# RTD.net
KiCad netlist of a schematic drawn in Altium Designer
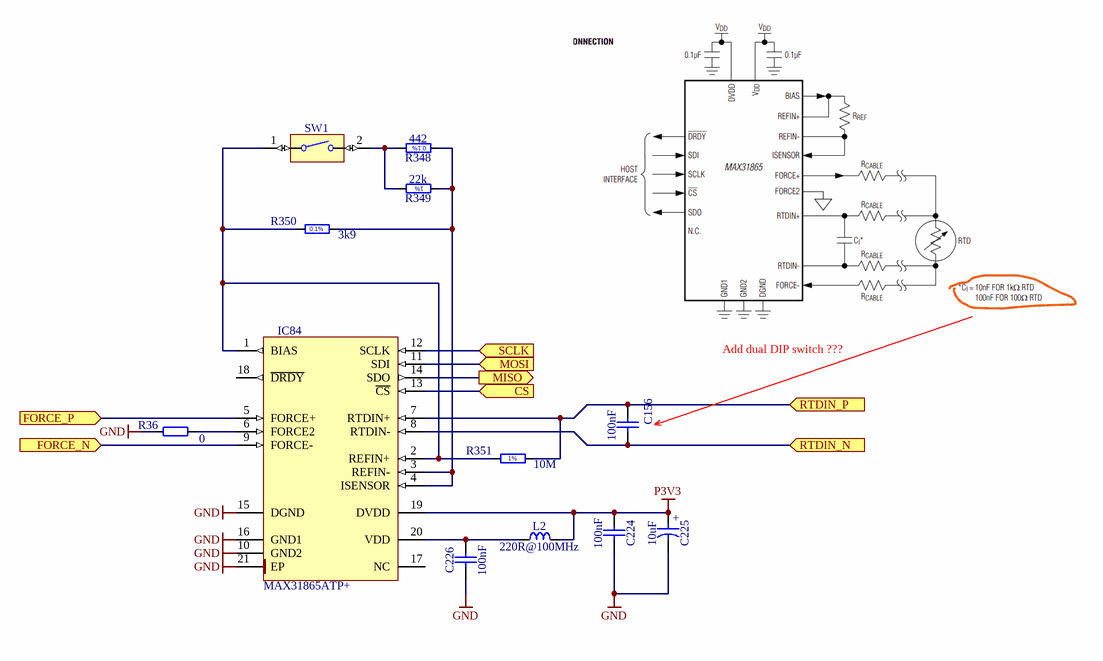
[diagram p0: RTD.SchDoc]

(export (version "E")
  (design (tool "Eeschema 10.0.6"))
  (components
    (comp (ref "C156")
      (value "100nF")
      (footprint "CAPC1005X55N")
      (description "Non-polarised capacitor")
      (fields
        (field (name "PART NUMBER") "CC0402_100NF_16V_10%_X5R")
        (field (name "VOLTAGE") "16V")
        (field (name "AUTHOR") "CERN DEM JLC")
      )
      (libsource (lib "Capacitors") (part "Capacitor - non polarized"))
    )
    (comp (ref "C224")
      (value "100nF")
      (footprint "CAPC1005X55N")
      (description "Non-polarised capacitor")
      (fields
        (field (name "PART NUMBER") "CC0402_100NF_16V_10%_X5R")
        (field (name "VOLTAGE") "16V")
        (field (name "AUTHOR") "CERN DEM JLC")
      )
      (libsource (lib "Capacitors") (part "Capacitor - non polarized"))
    )
    (comp (ref "C225")
      (value "10uF")
      (footprint "CAPMP3216X180N")
      (description "Polarised capacitor")
      (fields
        (field (name "PART NUMBER") "CTE3216-18_10UF_16V_20%_AVX_TCJ")
        (field (name "VOLTAGE") "16V")
        (field (name "AUTHOR") "CERN DEM JLC")
      )
      (libsource (lib "Capacitors") (part "Capacitor - polarized"))
    )
    (comp (ref "C226")
      (value "100nF")
      (footprint "CAPC1005X55N")
      (description "Non-polarised capacitor")
      (fields
        (field (name "PART NUMBER") "CC0402_100NF_16V_10%_X5R")
        (field (name "VOLTAGE") "16V")
        (field (name "AUTHOR") "CERN DEM JLC")
      )
      (libsource (lib "Capacitors") (part "Capacitor - non polarized"))
    )
    (comp (ref "IC84")
      (value "MAX31865ATP+")
      (footprint "QFN65P500X500X80-21N-S335")
      (description "RTD-to-Digital Converter")
      (fields (field (name "MANUFACTURER") "MAXIM") (field (name "AUTHOR") "CERN DEM MR"))
      (libsource (lib "ICs And Semiconductors") (part "MAX31865ATP+"))
    )
    (comp (ref "L2")
      (value "220R@100MHz")
      (footprint "INDC1005X55N")
      (description "Inductor")
      (fields
        (field (name "PART NUMBER") "IND0402_MURATA_BLM15HB221SN1")
        (field (name "POWER") "250mA")
        (field (name "AUTHOR") "CERN DEM JLC")
      )
      (libsource (lib "Inductors & Transformers") (part "Inductor"))
    )
    (comp (ref "R36")
      (value "0")
      (footprint "RESC1005X40N")
      (description "Resistor")
      (fields
        (field (name "PART NUMBER") "R0402_0R_JUMPER")
        (field (name "MANUFACTURER") "GENERIC")
        (field (name "AUTHOR") "CERN DEM JLC")
      )
      (libsource (lib "Resistors") (part "Resistor"))
    )
    (comp (ref "R348")
      (value "442")
      (footprint "RESC1608X55N")
      (description "Resistor - 0.1%")
      (fields
        (field (name "PART NUMBER") "R0603_442R_0.1%_0.063W_25PPM")
        (field (name "POWER") "0.063W")
        (field (name "AUTHOR") "GK")
      )
      (libsource (lib "LIBRARY_SCH") (part "RES_0603_442R_0.1%_25ppm"))
    )
    (comp (ref "R349")
      (value "22k")
      (footprint "RESC1005X40N")
      (description "Resistor - 1%")
      (fields
        (field (name "PART NUMBER") "R0402_22K_1%_0.0625W_100PPM")
        (field (name "POWER") "0.0625W")
        (field (name "AUTHOR") "CERN DEM JLC")
      )
      (libsource (lib "Resistors") (part "Resistor - 1%"))
    )
    (comp (ref "R350")
      (value "3k9")
      (footprint "RESC1608X55N")
      (description "Resistor - 0.1%")
      (fields
        (field (name "PART NUMBER") "R0603_3k9_0.1%_0.063W_10PPM")
        (field (name "POWER") "0.063W")
        (field (name "AUTHOR") "GK")
      )
      (libsource (lib "LIBRARY_SCH") (part "RES_0603_3k9_0.1%_10ppm"))
    )
    (comp (ref "R351")
      (value "10M")
      (footprint "RESC1608X55N")
      (description "Resistor - 1%")
      (fields
        (field (name "PART NUMBER") "R0603_10M_1%_0.1W_100PPM")
        (field (name "POWER") "0.1W")
        (field (name "AUTHOR") "CERN DEM JLC")
      )
      (libsource (lib "Resistors") (part "Resistor - 1%"))
    )
    (comp (ref "SW1")
      (value "Switch")
      (footprint "SW_OMRON_A6SN-1101")
      (description "1 Ways SPST DIP Switch")
      (fields
        (field (name "PART NUMBER") "SW_OMRON_A6SN-1101")
        (field (name "MANUFACTURER") "OMRON")
        (field (name "AUTHOR") "CERN DEM JLC")
      )
      (libsource (lib "Eletro-mechanical") (part "SW 1x SPST DIP Switch"))
    )
  )
  (nets
    (net (code "1") (name "/CS") (class "Default")
      (node (ref "IC84") (pin "13") (pinfunction "~{CS}_13") (pintype "input"))
    )
    (net (code "2") (name "/FORCE_N") (class "Default")
      (node (ref "IC84") (pin "9") (pinfunction "FORCE-_9") (pintype "input"))
    )
    (net (code "3") (name "/FORCE_P") (class "Default")
      (node (ref "IC84") (pin "5") (pinfunction "FORCE+_5") (pintype "input"))
    )
    (net (code "4") (name "/MISO") (class "Default")
      (node (ref "IC84") (pin "14") (pinfunction "SDO_14") (pintype "output"))
    )
    (net (code "5") (name "/MOSI") (class "Default")
      (node (ref "IC84") (pin "11") (pinfunction "SDI_11") (pintype "input"))
    )
    (net (code "6") (name "/RTDIN_N") (class "Default")
      (node (ref "C156") (pin "2") (pinfunction "2_2") (pintype "passive"))
      (node (ref "IC84") (pin "8") (pinfunction "RTDIN-_8") (pintype "input"))
    )
    (net (code "7") (name "/RTDIN_P") (class "Default")
      (node (ref "C156") (pin "1") (pinfunction "1_1") (pintype "passive"))
      (node (ref "IC84") (pin "7") (pinfunction "RTDIN+_7") (pintype "input"))
      (node (ref "R351") (pin "2") (pinfunction "2_2") (pintype "passive"))
    )
    (net (code "8") (name "/SCLK") (class "Default")
      (node (ref "IC84") (pin "12") (pinfunction "SCLK_12") (pintype "input"))
    )
    (net (code "9") (name "GND") (class "Default")
      (node (ref "C224") (pin "2") (pinfunction "2_2") (pintype "passive"))
      (node (ref "C225") (pin "2") (pinfunction "2_2") (pintype "passive"))
      (node (ref "C226") (pin "1") (pinfunction "1_1") (pintype "passive"))
      (node (ref "IC84") (pin "10") (pinfunction "GND2_10") (pintype "power_in"))
      (node (ref "IC84") (pin "15") (pinfunction "DGND_15") (pintype "power_in"))
      (node (ref "IC84") (pin "16") (pinfunction "GND1_16") (pintype "power_in"))
      (node (ref "IC84") (pin "21") (pinfunction "EP_21") (pintype "power_in"))
      (node (ref "R36") (pin "1") (pinfunction "1_1") (pintype "passive"))
    )
    (net (code "10") (name "Net-(IC84-BIAS)") (class "Default")
      (node (ref "IC84") (pin "1") (pinfunction "BIAS_1") (pintype "output"))
      (node (ref "IC84") (pin "2") (pinfunction "REFIN+_2") (pintype "input"))
      (node (ref "R350") (pin "1") (pinfunction "1_1") (pintype "passive"))
      (node (ref "R351") (pin "1") (pinfunction "1_1") (pintype "passive"))
      (node (ref "SW1") (pin "1") (pinfunction "1_1") (pintype "bidirectional"))
    )
    (net (code "11") (name "Net-(IC84-FORCE2)") (class "Default")
      (node (ref "IC84") (pin "6") (pinfunction "FORCE2_6") (pintype "input"))
      (node (ref "R36") (pin "2") (pinfunction "2_2") (pintype "passive"))
    )
    (net (code "12") (name "Net-(IC84-ISENSOR)") (class "Default")
      (node (ref "IC84") (pin "3") (pinfunction "REFIN-_3") (pintype "input"))
      (node (ref "IC84") (pin "4") (pinfunction "ISENSOR_4") (pintype "input"))
      (node (ref "R348") (pin "1") (pinfunction "1_1") (pintype "passive"))
      (node (ref "R349") (pin "1") (pinfunction "1_1") (pintype "passive"))
      (node (ref "R350") (pin "2") (pinfunction "2_2") (pintype "passive"))
    )
    (net (code "13") (name "Net-(IC84-VDD)") (class "Default")
      (node (ref "C226") (pin "2") (pinfunction "2_2") (pintype "passive"))
      (node (ref "IC84") (pin "20") (pinfunction "VDD_20") (pintype "power_in"))
      (node (ref "L2") (pin "1") (pinfunction "1_1") (pintype "passive"))
    )
    (net (code "14") (name "Net-(R348-Pad2)") (class "Default")
      (node (ref "R348") (pin "2") (pinfunction "2_2") (pintype "passive"))
      (node (ref "R349") (pin "2") (pinfunction "2_2") (pintype "passive"))
      (node (ref "SW1") (pin "2") (pinfunction "2_2") (pintype "bidirectional"))
    )
    (net (code "15") (name "P3V3") (class "Default")
      (node (ref "C224") (pin "1") (pinfunction "1_1") (pintype "passive"))
      (node (ref "C225") (pin "1") (pinfunction "1_1") (pintype "passive"))
      (node (ref "IC84") (pin "19") (pinfunction "DVDD_19") (pintype "power_in"))
      (node (ref "L2") (pin "2") (pinfunction "2_2") (pintype "passive"))
    )
    (net (code "16") (name "unconnected-(IC84-NC-Pad17)") (class "Default")
      (node (ref "IC84") (pin "17") (pinfunction "NC_17") (pintype "passive"))
    )
    (net (code "17") (name "unconnected-(IC84-~{DRDY}-Pad18)") (class "Default")
      (node (ref "IC84") (pin "18") (pinfunction "~{DRDY}_18") (pintype "output"))
    )
  )
)
